# Sheet1.net
KiCad netlist of a schematic drawn in Altium Designer
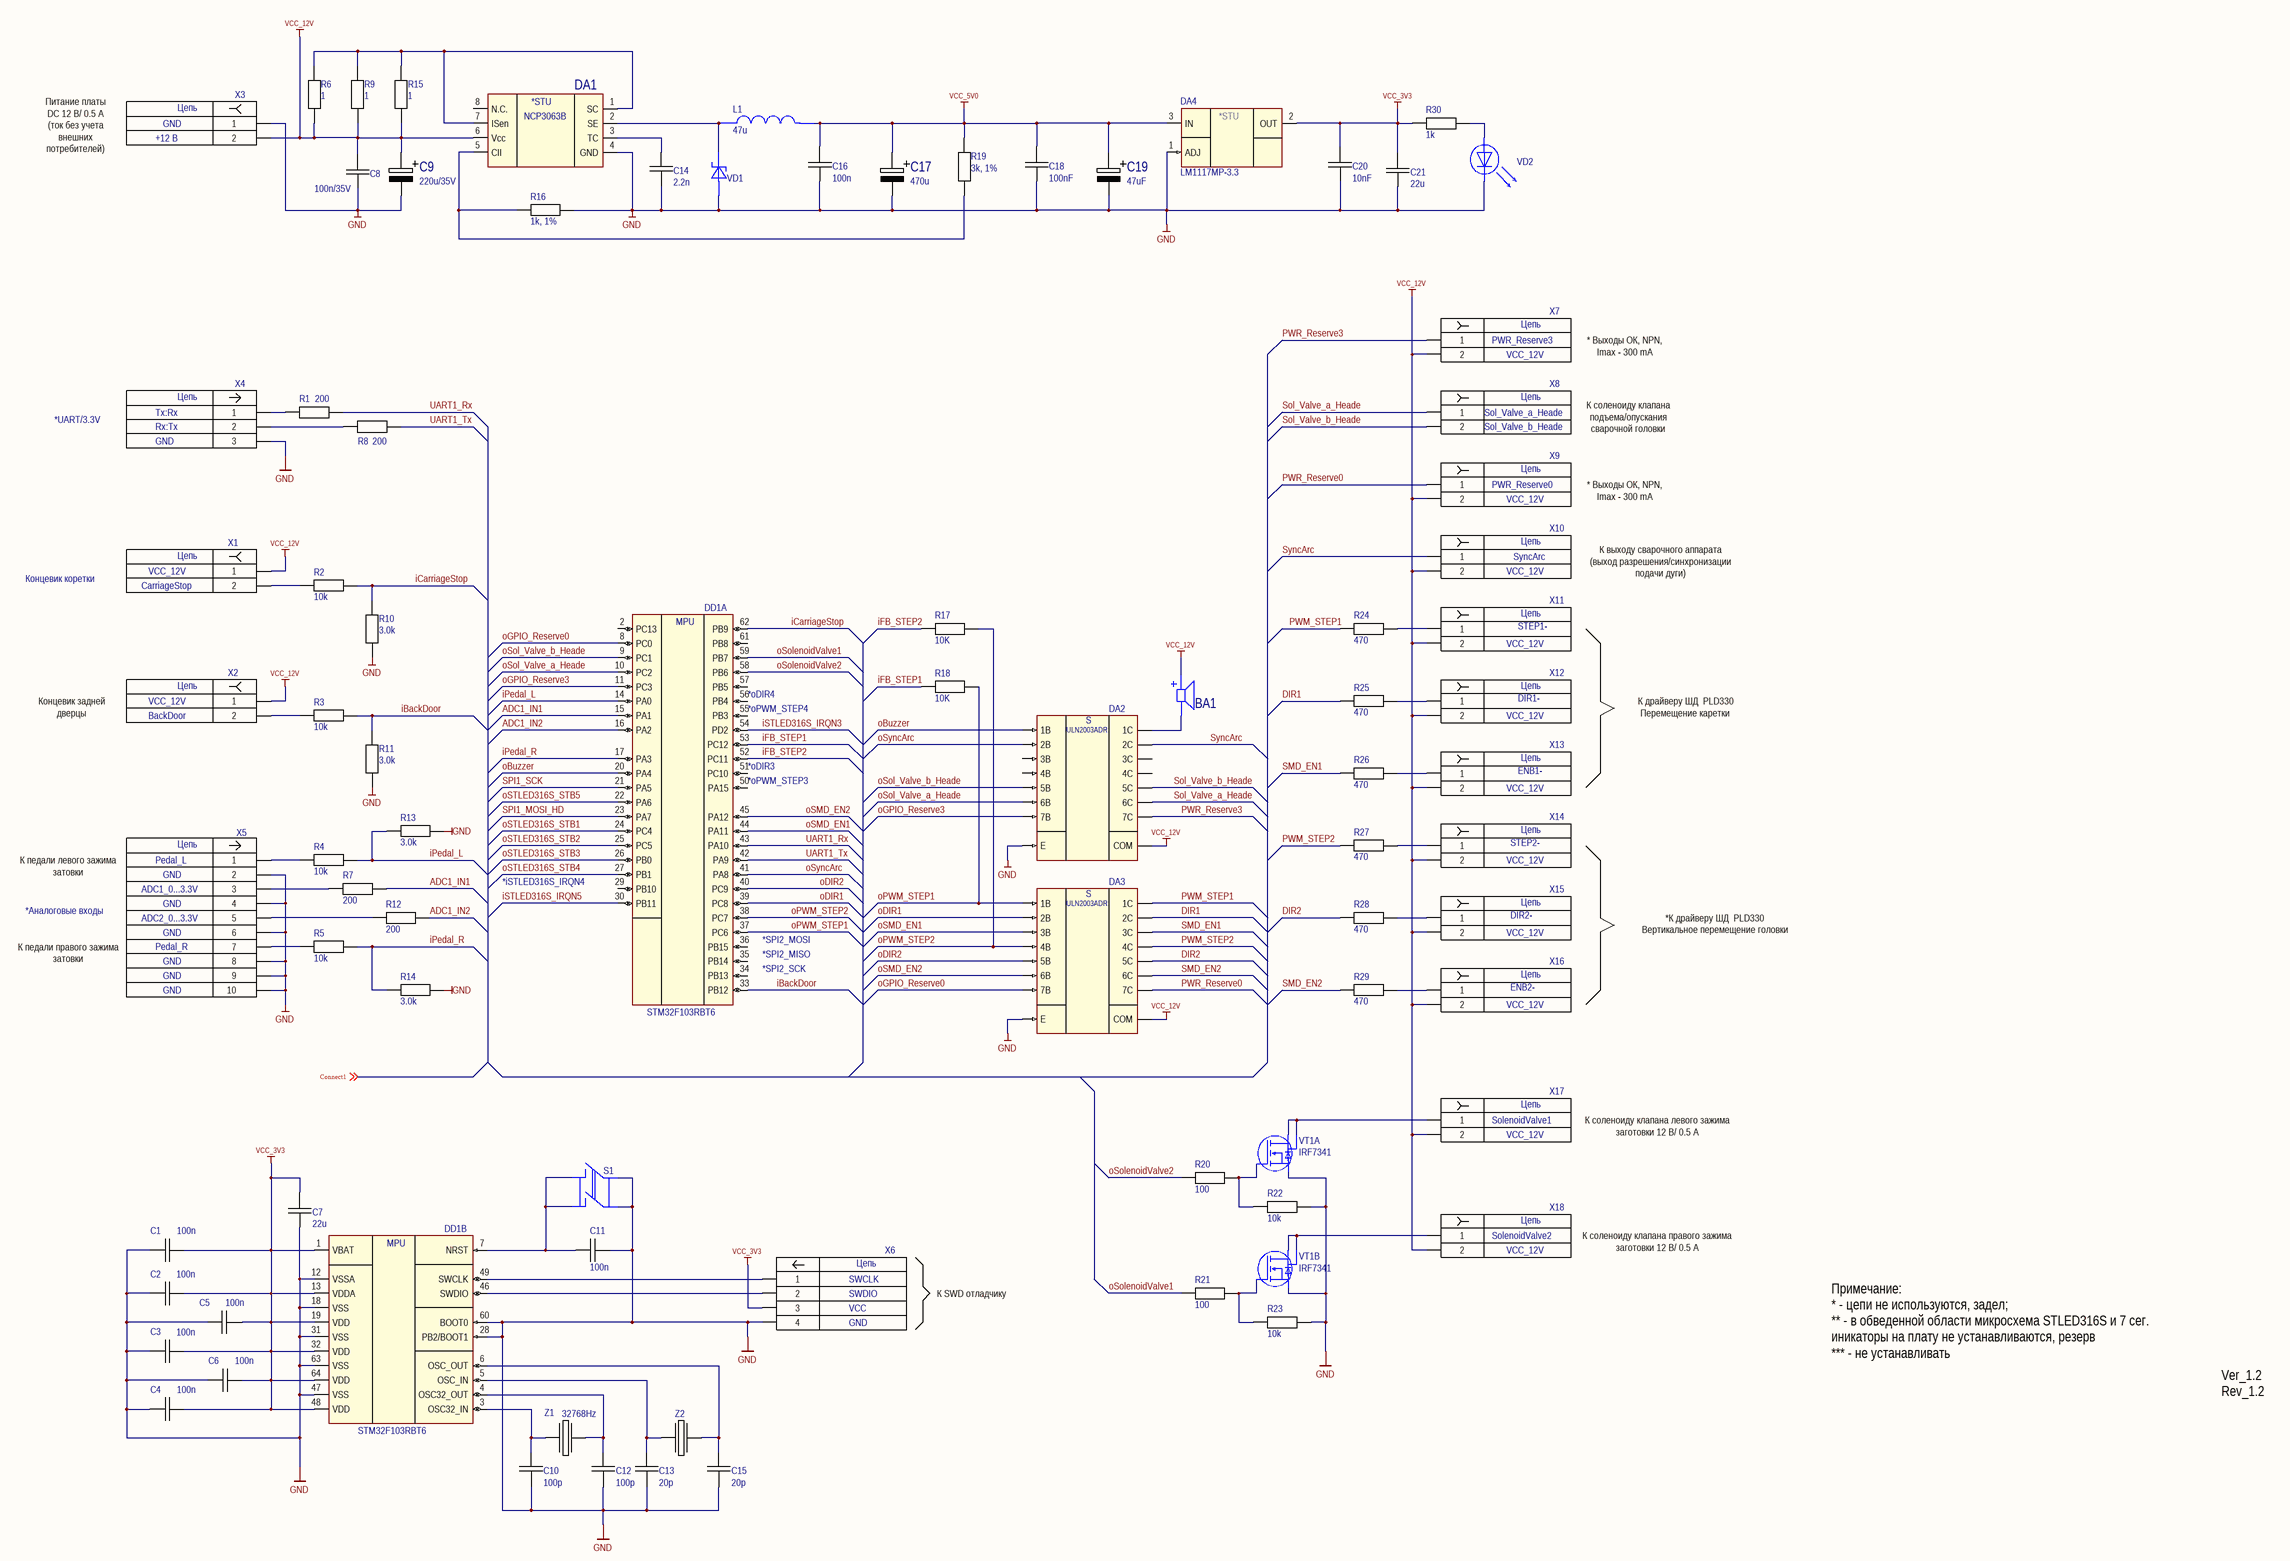
[diagram p0: Sheet1.SchDoc]

(export (version "E")
  (design (tool "Eeschema 10.0.6"))
  (components
    (comp (ref "BA1")
      (value "Buzzer_HCM1212A")
      (footprint "Buzzer_HCM1212A")
      (libsource (lib "Библиотека элементов") (part "Buzzer_HCM1212A"))
    )
    (comp (ref "C1")
      (value "100n")
      (footprint "Capacitor_0805")
      (libsource (lib "Библиотека элементов") (part "Capacitor_0805"))
    )
    (comp (ref "C2")
      (value "100n")
      (footprint "Capacitor_0805")
      (libsource (lib "Библиотека элементов") (part "Capacitor_0805"))
    )
    (comp (ref "C3")
      (value "100n")
      (footprint "Capacitor_0805")
      (libsource (lib "Библиотека элементов") (part "Capacitor_0805"))
    )
    (comp (ref "C4")
      (value "100n")
      (footprint "Capacitor_0805")
      (libsource (lib "Библиотека элементов") (part "Capacitor_0805"))
    )
    (comp (ref "C5")
      (value "100n")
      (footprint "Capacitor_0805")
      (libsource (lib "Библиотека элементов") (part "Capacitor_0805"))
    )
    (comp (ref "C6")
      (value "100n")
      (footprint "Capacitor_0805")
      (libsource (lib "Библиотека элементов") (part "Capacitor_0805"))
    )
    (comp (ref "C7")
      (value "22u")
      (footprint "CAPACITOR_1206")
      (libsource (lib "Библиотека элементов") (part "Capacitor_1206"))
    )
    (comp (ref "C8")
      (value "100n/35V")
      (footprint "Capacitor_0805")
      (libsource (lib "Библиотека элементов") (part "Capacitor_0805"))
    )
    (comp (ref "C9")
      (value "220u/35V")
      (footprint "Capacitor_Electrolit_6.3x11")
      (libsource (lib "Библиотека элементов") (part "Capacitor+_6.3x11"))
    )
    (comp (ref "C10")
      (value "100p")
      (footprint "Capacitor_0805")
      (libsource (lib "Библиотека элементов") (part "Capacitor_0805"))
    )
    (comp (ref "C11")
      (value "100n")
      (footprint "Capacitor_0805")
      (libsource (lib "Библиотека элементов") (part "Capacitor_0805"))
    )
    (comp (ref "C12")
      (value "100p")
      (footprint "Capacitor_0805")
      (libsource (lib "Библиотека элементов") (part "Capacitor_0805"))
    )
    (comp (ref "C13")
      (value "20p")
      (footprint "Capacitor_0805")
      (libsource (lib "Библиотека элементов") (part "Capacitor_0805"))
    )
    (comp (ref "C14")
      (value "2.2n")
      (footprint "Capacitor_0805")
      (libsource (lib "Библиотека элементов") (part "Capacitor_0805"))
    )
    (comp (ref "C15")
      (value "20p")
      (footprint "Capacitor_0805")
      (libsource (lib "Библиотека элементов") (part "Capacitor_0805"))
    )
    (comp (ref "C16")
      (value "100n")
      (footprint "Capacitor_0805")
      (libsource (lib "Библиотека элементов") (part "Capacitor_0805"))
    )
    (comp (ref "C17")
      (value "470u")
      (footprint "Capacitor_Electrolit_6.3x11")
      (libsource (lib "Библиотека элементов") (part "Capacitor+_6.3x11"))
    )
    (comp (ref "C18")
      (value "100nF")
      (footprint "Capacitor_0805")
      (libsource (lib "Библиотека элементов") (part "Capacitor_0805"))
    )
    (comp (ref "C19")
      (value "47uF")
      (footprint "Capacitor_Electrolit_6.3x11")
      (libsource (lib "Библиотека элементов") (part "Capacitor+_6.3x11"))
    )
    (comp (ref "C20")
      (value "10nF")
      (footprint "Capacitor_0805")
      (libsource (lib "Библиотека элементов") (part "Capacitor_0805"))
    )
    (comp (ref "C21")
      (value "22u")
      (footprint "CAPACITOR_1206")
      (libsource (lib "Библиотека элементов") (part "Capacitor_1206"))
    )
    (comp (ref "DA1")
      (value "NCP3063B")
      (footprint "SOIC8")
      (libsource (lib "Библиотека элементов") (part "NCP3063B"))
    )
    (comp (ref "DA2")
      (value "ULN2003")
      (footprint "MCP3208_SOIC16")
      (libsource (lib "Библиотека элементов") (part "ULN2003"))
    )
    (comp (ref "DA3")
      (value "ULN2003")
      (footprint "MCP3208_SOIC16")
      (libsource (lib "Библиотека элементов") (part "ULN2003"))
    )
    (comp (ref "DA4")
      (value "LM1117MP-3.3")
      (footprint "NCP1117_SOT223")
      (libsource (lib "Библиотека элементов") (part "LM1117MP-3.3"))
    )
    (comp (ref "DD1")
      (value "STM32F103RBT6")
      (footprint "STM32F103RBT6_LQFP64")
      (libsource (lib "Библиотека элементов") (part "STM32F103RBT6"))
    )
    (comp (ref "L1")
      (value "47u")
      (footprint "INDUCTOR_CDRH8D28")
      (libsource (lib "Библиотека элементов") (part "Indluctor_CDRH8D28"))
    )
    (comp (ref "R1")
      (value "200")
      (footprint "RESISTOR_SMD0805")
      (libsource (lib "Библиотека элементов") (part "Resistor_0805"))
    )
    (comp (ref "R2")
      (value "10k")
      (footprint "RESISTOR_SMD0805")
      (libsource (lib "Библиотека элементов") (part "Resistor_0805"))
    )
    (comp (ref "R3")
      (value "10k")
      (footprint "RESISTOR_SMD0805")
      (libsource (lib "Библиотека элементов") (part "Resistor_0805"))
    )
    (comp (ref "R4")
      (value "10k")
      (footprint "RESISTOR_SMD0805")
      (libsource (lib "Библиотека элементов") (part "Resistor_0805"))
    )
    (comp (ref "R5")
      (value "10k")
      (footprint "RESISTOR_SMD0805")
      (libsource (lib "Библиотека элементов") (part "Resistor_0805"))
    )
    (comp (ref "R6")
      (value "1")
      (footprint "RESISTOR_SMD0805")
      (libsource (lib "Библиотека элементов") (part "Resistor_0805"))
    )
    (comp (ref "R7")
      (value "200")
      (footprint "RESISTOR_SMD0805")
      (libsource (lib "Библиотека элементов") (part "Resistor_0805"))
    )
    (comp (ref "R8")
      (value "200")
      (footprint "RESISTOR_SMD0805")
      (libsource (lib "Библиотека элементов") (part "Resistor_0805"))
    )
    (comp (ref "R9")
      (value "1")
      (footprint "RESISTOR_SMD0805")
      (libsource (lib "Библиотека элементов") (part "Resistor_0805"))
    )
    (comp (ref "R10")
      (value "3.0k")
      (footprint "RESISTOR_SMD0805")
      (libsource (lib "Библиотека элементов") (part "Resistor_0805"))
    )
    (comp (ref "R11")
      (value "3.0k")
      (footprint "RESISTOR_SMD0805")
      (libsource (lib "Библиотека элементов") (part "Resistor_0805"))
    )
    (comp (ref "R12")
      (value "200")
      (footprint "RESISTOR_SMD0805")
      (libsource (lib "Библиотека элементов") (part "Resistor_0805"))
    )
    (comp (ref "R13")
      (value "3.0k")
      (footprint "RESISTOR_SMD0805")
      (libsource (lib "Библиотека элементов") (part "Resistor_0805"))
    )
    (comp (ref "R14")
      (value "3.0k")
      (footprint "RESISTOR_SMD0805")
      (libsource (lib "Библиотека элементов") (part "Resistor_0805"))
    )
    (comp (ref "R15")
      (value "1")
      (footprint "RESISTOR_SMD0805")
      (libsource (lib "Библиотека элементов") (part "Resistor_0805"))
    )
    (comp (ref "R16")
      (value "1k, 1%")
      (footprint "RESISTOR_SMD0805")
      (libsource (lib "Библиотека элементов") (part "Resistor_0805"))
    )
    (comp (ref "R17")
      (value "10K")
      (footprint "RESISTOR_SMD0805")
      (libsource (lib "Библиотека элементов") (part "Resistor_0805"))
    )
    (comp (ref "R18")
      (value "10K")
      (footprint "RESISTOR_SMD0805")
      (libsource (lib "Библиотека элементов") (part "Resistor_0805"))
    )
    (comp (ref "R19")
      (value "3k, 1%")
      (footprint "RESISTOR_SMD0805")
      (libsource (lib "Библиотека элементов") (part "Resistor_0805"))
    )
    (comp (ref "R20")
      (value "100")
      (footprint "RESISTOR_SMD0805")
      (libsource (lib "Библиотека элементов") (part "Resistor_0805"))
    )
    (comp (ref "R21")
      (value "100")
      (footprint "RESISTOR_SMD0805")
      (libsource (lib "Библиотека элементов") (part "Resistor_0805"))
    )
    (comp (ref "R22")
      (value "10k")
      (footprint "RESISTOR_SMD0805")
      (libsource (lib "Библиотека элементов") (part "Resistor_0805"))
    )
    (comp (ref "R23")
      (value "10k")
      (footprint "RESISTOR_SMD0805")
      (libsource (lib "Библиотека элементов") (part "Resistor_0805"))
    )
    (comp (ref "R24")
      (value "470")
      (footprint "RESISTOR_SMD0805")
      (libsource (lib "Библиотека элементов") (part "Resistor_0805"))
    )
    (comp (ref "R25")
      (value "470")
      (footprint "RESISTOR_SMD0805")
      (libsource (lib "Библиотека элементов") (part "Resistor_0805"))
    )
    (comp (ref "R26")
      (value "470")
      (footprint "RESISTOR_SMD0805")
      (libsource (lib "Библиотека элементов") (part "Resistor_0805"))
    )
    (comp (ref "R27")
      (value "470")
      (footprint "RESISTOR_SMD0805")
      (libsource (lib "Библиотека элементов") (part "Resistor_0805"))
    )
    (comp (ref "R28")
      (value "470")
      (footprint "RESISTOR_SMD0805")
      (libsource (lib "Библиотека элементов") (part "Resistor_0805"))
    )
    (comp (ref "R29")
      (value "470")
      (footprint "RESISTOR_SMD0805")
      (libsource (lib "Библиотека элементов") (part "Resistor_0805"))
    )
    (comp (ref "R30")
      (value "1k")
      (footprint "RESISTOR_SMD0805")
      (libsource (lib "") (part "Resistor_0805_1"))
    )
    (comp (ref "S1")
      (value "DTS-26 12x12x9.5")
      (footprint "Tact Switch_DTS-26_12x12x95")
      (libsource (lib "Библиотека элементов") (part "Tact_Switch_DTS-26_12x12x95"))
    )
    (comp (ref "VD1")
      (value "STPS1L30A")
      (footprint "DIODE_STPS1L30A")
      (libsource (lib "Библиотека элементов") (part "Diode_STPS1L30A"))
    )
    (comp (ref "VD2")
      (value "LED_FYL-3014GD1A")
      (footprint "LED_ FYL-3014GD1A")
      (libsource (lib "Библиотека элементов") (part "LED_FYL-3014GD1A"))
    )
    (comp (ref "VT1")
      (value "IRF7341")
      (footprint "IRF7341_SO-8/SOIC-8")
      (libsource (lib "Библиотека элементов") (part "IRF7341"))
    )
    (comp (ref "X1")
      (value "Connector_DG306-5.0-02P")
      (footprint "CONNECTOR_DG306-5.0-02P")
      (libsource (lib "Библиотека элементов") (part "Connector_DG306-5.0-02P"))
    )
    (comp (ref "X2")
      (value "Connector_DG306-5.0-02P")
      (footprint "CONNECTOR_DG306-5.0-02P")
      (libsource (lib "Библиотека элементов") (part "Connector_DG306-5.0-02P"))
    )
    (comp (ref "X3")
      (value "Connector_DG306-5.0-02P")
      (footprint "CONNECTOR_DG306-5.0-02P")
      (libsource (lib "Библиотека элементов") (part "Connector_DG306-5.0-02P"))
    )
    (comp (ref "X4")
      (value "Connector_PLS-3")
      (footprint "CONNECTOR_PLS-3")
      (libsource (lib "Библиотека элементов") (part "Connector_PLS-3"))
    )
    (comp (ref "X5")
      (value "Connector_PLD-10")
      (footprint "CONNECTOR_PLD-10")
      (libsource (lib "Библиотека элементов") (part "Connector_PLD-10"))
    )
    (comp (ref "X6")
      (value "Connector_PLS-4")
      (footprint "CONNECTOR_PLS-4")
      (libsource (lib "Библиотека элементов") (part "Connector_PLS-4"))
    )
    (comp (ref "X7")
      (value "Connector_DG306-5.0-02P")
      (footprint "CONNECTOR_DG306-5.0-02P")
      (libsource (lib "Библиотека элементов") (part "Connector_DG306-5.0-02P"))
    )
    (comp (ref "X8")
      (value "Connector_DG306-5.0-02P")
      (footprint "CONNECTOR_DG306-5.0-02P")
      (libsource (lib "Библиотека элементов") (part "Connector_DG306-5.0-02P"))
    )
    (comp (ref "X9")
      (value "Connector_DG306-5.0-02P")
      (footprint "CONNECTOR_DG306-5.0-02P")
      (libsource (lib "Библиотека элементов") (part "Connector_DG306-5.0-02P"))
    )
    (comp (ref "X10")
      (value "Connector_DG306-5.0-02P")
      (footprint "CONNECTOR_DG306-5.0-02P")
      (libsource (lib "Библиотека элементов") (part "Connector_DG306-5.0-02P"))
    )
    (comp (ref "X11")
      (value "Connector_DG306-5.0-02P")
      (footprint "CONNECTOR_DG306-5.0-02P")
      (libsource (lib "Библиотека элементов") (part "Connector_DG306-5.0-02P"))
    )
    (comp (ref "X12")
      (value "Connector_DG306-5.0-02P")
      (footprint "CONNECTOR_DG306-5.0-02P")
      (libsource (lib "Библиотека элементов") (part "Connector_DG306-5.0-02P"))
    )
    (comp (ref "X13")
      (value "Connector_DG306-5.0-02P")
      (footprint "CONNECTOR_DG306-5.0-02P")
      (libsource (lib "Библиотека элементов") (part "Connector_DG306-5.0-02P"))
    )
    (comp (ref "X14")
      (value "Connector_DG306-5.0-02P")
      (footprint "CONNECTOR_DG306-5.0-02P")
      (libsource (lib "Библиотека элементов") (part "Connector_DG306-5.0-02P"))
    )
    (comp (ref "X15")
      (value "Connector_DG306-5.0-02P")
      (footprint "CONNECTOR_DG306-5.0-02P")
      (libsource (lib "Библиотека элементов") (part "Connector_DG306-5.0-02P"))
    )
    (comp (ref "X16")
      (value "Connector_DG306-5.0-02P")
      (footprint "CONNECTOR_DG306-5.0-02P")
      (libsource (lib "Библиотека элементов") (part "Connector_DG306-5.0-02P"))
    )
    (comp (ref "X17")
      (value "Connector_DG306-5.0-02P")
      (footprint "CONNECTOR_DG306-5.0-02P")
      (libsource (lib "Библиотека элементов") (part "Connector_DG306-5.0-02P"))
    )
    (comp (ref "X18")
      (value "Connector_DG306-5.0-02P")
      (footprint "CONNECTOR_DG306-5.0-02P")
      (libsource (lib "Библиотека элементов") (part "Connector_DG306-5.0-02P"))
    )
    (comp (ref "Z1")
      (value "32768Hz")
      (footprint "Quartz_32768kHz")
      (libsource (lib "Библиотека элементов") (part "Quartz_32678Hz"))
    )
    (comp (ref "Z2")
      (value "Quartz_KX-9A")
      (footprint "Quartz_KX-9")
      (libsource (lib "Библиотека элементов") (part "Quartz_KX-9A"))
    )
  )
  (nets
    (net (code "1") (name "/ADC1_IN1") (class "Default")
      (node (ref "DD1") (pin "15") (pinfunction "PA1_15") (pintype "bidirectional"))
      (node (ref "R7") (pin "1") (pinfunction "1_1") (pintype "passive"))
    )
    (net (code "2") (name "/ADC1_IN2") (class "Default")
      (node (ref "DD1") (pin "16") (pinfunction "PA2_16") (pintype "bidirectional"))
      (node (ref "R12") (pin "1") (pinfunction "1_1") (pintype "passive"))
    )
    (net (code "3") (name "/DIR1") (class "Default")
      (node (ref "DA3") (pin "15") (pinfunction "2C_15") (pintype "open_collector"))
      (node (ref "R25") (pin "2") (pinfunction "2_2") (pintype "passive"))
    )
    (net (code "4") (name "/DIR2") (class "Default")
      (node (ref "DA3") (pin "12") (pinfunction "5C_12") (pintype "open_collector"))
      (node (ref "R28") (pin "2") (pinfunction "2_2") (pintype "passive"))
    )
    (net (code "5") (name "/PWM_STEP1") (class "Default")
      (node (ref "DA3") (pin "16") (pinfunction "1C_16") (pintype "open_collector"))
      (node (ref "R24") (pin "2") (pinfunction "2_2") (pintype "passive"))
    )
    (net (code "6") (name "/PWM_STEP2") (class "Default")
      (node (ref "DA3") (pin "13") (pinfunction "4C_13") (pintype "open_collector"))
      (node (ref "R27") (pin "2") (pinfunction "2_2") (pintype "passive"))
    )
    (net (code "7") (name "/PWR_Reserve0") (class "Default")
      (node (ref "DA3") (pin "10") (pinfunction "7C_10") (pintype "open_collector"))
      (node (ref "X9") (pin "1") (pinfunction "1_1") (pintype "passive"))
    )
    (net (code "8") (name "/PWR_Reserve3") (class "Default")
      (node (ref "DA2") (pin "10") (pinfunction "7C_10") (pintype "open_collector"))
      (node (ref "X7") (pin "1") (pinfunction "1_1") (pintype "passive"))
    )
    (net (code "9") (name "/SMD_EN1") (class "Default")
      (node (ref "DA3") (pin "14") (pinfunction "3C_14") (pintype "open_collector"))
      (node (ref "R26") (pin "2") (pinfunction "2_2") (pintype "passive"))
    )
    (net (code "10") (name "/SMD_EN2") (class "Default")
      (node (ref "DA3") (pin "11") (pinfunction "6C_11") (pintype "open_collector"))
      (node (ref "R29") (pin "2") (pinfunction "2_2") (pintype "passive"))
    )
    (net (code "11") (name "/SPI1_MOSI_HD") (class "Default")
      (node (ref "DD1") (pin "23") (pinfunction "PA7_23") (pintype "bidirectional"))
    )
    (net (code "12") (name "/SPI1_SCK") (class "Default")
      (node (ref "DD1") (pin "21") (pinfunction "PA5_21") (pintype "bidirectional"))
    )
    (net (code "13") (name "/Sol_Valve_a_Heade") (class "Default")
      (node (ref "DA2") (pin "11") (pinfunction "6C_11") (pintype "open_collector"))
      (node (ref "X8") (pin "1") (pinfunction "1_1") (pintype "passive"))
    )
    (net (code "14") (name "/Sol_Valve_b_Heade") (class "Default")
      (node (ref "DA2") (pin "12") (pinfunction "5C_12") (pintype "open_collector"))
      (node (ref "X8") (pin "2") (pinfunction "2_2") (pintype "passive"))
    )
    (net (code "15") (name "/SyncArc") (class "Default")
      (node (ref "DA2") (pin "15") (pinfunction "2C_15") (pintype "open_collector"))
      (node (ref "X10") (pin "1") (pinfunction "1_1") (pintype "passive"))
    )
    (net (code "16") (name "/UART1_Rx") (class "Default")
      (node (ref "DD1") (pin "43") (pinfunction "PA10_43") (pintype "bidirectional"))
      (node (ref "R1") (pin "1") (pinfunction "1_1") (pintype "passive"))
    )
    (net (code "17") (name "/UART1_Tx") (class "Default")
      (node (ref "DD1") (pin "42") (pinfunction "PA9_42") (pintype "bidirectional"))
      (node (ref "R8") (pin "1") (pinfunction "1_1") (pintype "passive"))
    )
    (net (code "18") (name "/iBackDoor") (class "Default")
      (node (ref "DD1") (pin "33") (pinfunction "PB12_33") (pintype "bidirectional"))
      (node (ref "R11") (pin "2") (pinfunction "2_2") (pintype "passive"))
      (node (ref "R3") (pin "1") (pinfunction "1_1") (pintype "passive"))
    )
    (net (code "19") (name "/iCarriageStop") (class "Default")
      (node (ref "DD1") (pin "62") (pinfunction "PB9_62") (pintype "bidirectional"))
      (node (ref "R10") (pin "2") (pinfunction "2_2") (pintype "passive"))
      (node (ref "R2") (pin "1") (pinfunction "1_1") (pintype "passive"))
    )
    (net (code "20") (name "/iFB_STEP1") (class "Default")
      (node (ref "DD1") (pin "53") (pinfunction "PC12_53") (pintype "bidirectional"))
      (node (ref "R18") (pin "1") (pinfunction "1_1") (pintype "passive"))
    )
    (net (code "21") (name "/iFB_STEP2") (class "Default")
      (node (ref "DD1") (pin "52") (pinfunction "PC11_52") (pintype "bidirectional"))
      (node (ref "R17") (pin "1") (pinfunction "1_1") (pintype "passive"))
    )
    (net (code "22") (name "/iPedal_L") (class "Default")
      (node (ref "DD1") (pin "14") (pinfunction "PA0_14") (pintype "bidirectional"))
      (node (ref "R13") (pin "2") (pinfunction "2_2") (pintype "passive"))
      (node (ref "R4") (pin "1") (pinfunction "1_1") (pintype "passive"))
    )
    (net (code "23") (name "/iPedal_R") (class "Default")
      (node (ref "DD1") (pin "17") (pinfunction "PA3_17") (pintype "bidirectional"))
      (node (ref "R14") (pin "2") (pinfunction "2_2") (pintype "passive"))
      (node (ref "R5") (pin "1") (pinfunction "1_1") (pintype "passive"))
    )
    (net (code "24") (name "/iSTLED316S_IRQN3") (class "Default")
      (node (ref "DD1") (pin "54") (pinfunction "PD2_54") (pintype "bidirectional"))
    )
    (net (code "25") (name "/iSTLED316S_IRQN5") (class "Default")
      (node (ref "DD1") (pin "30") (pinfunction "PB11_30") (pintype "bidirectional"))
    )
    (net (code "26") (name "/oBuzzer") (class "Default")
      (node (ref "DA2") (pin "1") (pinfunction "1B_1") (pintype "input"))
      (node (ref "DD1") (pin "20") (pinfunction "PA4_20") (pintype "bidirectional"))
    )
    (net (code "27") (name "/oDIR1") (class "Default")
      (node (ref "DA3") (pin "2") (pinfunction "2B_2") (pintype "input"))
      (node (ref "DD1") (pin "39") (pinfunction "PC8_39") (pintype "bidirectional"))
    )
    (net (code "28") (name "/oDIR2") (class "Default")
      (node (ref "DA3") (pin "5") (pinfunction "5B_5") (pintype "input"))
      (node (ref "DD1") (pin "40") (pinfunction "PC9_40") (pintype "bidirectional"))
    )
    (net (code "29") (name "/oGPIO_Reserve0") (class "Default")
      (node (ref "DA3") (pin "7") (pinfunction "7B_7") (pintype "input"))
      (node (ref "DD1") (pin "8") (pinfunction "PC0_8") (pintype "bidirectional"))
    )
    (net (code "30") (name "/oGPIO_Reserve3") (class "Default")
      (node (ref "DA2") (pin "7") (pinfunction "7B_7") (pintype "input"))
      (node (ref "DD1") (pin "11") (pinfunction "PC3_11") (pintype "bidirectional"))
    )
    (net (code "31") (name "/oPWM_STEP1") (class "Default")
      (node (ref "DA3") (pin "1") (pinfunction "1B_1") (pintype "input"))
      (node (ref "DD1") (pin "37") (pinfunction "PC6_37") (pintype "bidirectional"))
      (node (ref "R18") (pin "2") (pinfunction "2_2") (pintype "passive"))
    )
    (net (code "32") (name "/oPWM_STEP2") (class "Default")
      (node (ref "DA3") (pin "4") (pinfunction "4B_4") (pintype "input"))
      (node (ref "DD1") (pin "38") (pinfunction "PC7_38") (pintype "bidirectional"))
      (node (ref "R17") (pin "2") (pinfunction "2_2") (pintype "passive"))
    )
    (net (code "33") (name "/oSMD_EN1") (class "Default")
      (node (ref "DA3") (pin "3") (pinfunction "3B_3") (pintype "input"))
      (node (ref "DD1") (pin "44") (pinfunction "PA11_44") (pintype "bidirectional"))
    )
    (net (code "34") (name "/oSMD_EN2") (class "Default")
      (node (ref "DA3") (pin "6") (pinfunction "6B_6") (pintype "input"))
      (node (ref "DD1") (pin "45") (pinfunction "PA12_45") (pintype "bidirectional"))
    )
    (net (code "35") (name "/oSTLED316S_STB1") (class "Default")
      (node (ref "DD1") (pin "24") (pinfunction "PC4_24") (pintype "bidirectional"))
    )
    (net (code "36") (name "/oSTLED316S_STB2") (class "Default")
      (node (ref "DD1") (pin "25") (pinfunction "PC5_25") (pintype "bidirectional"))
    )
    (net (code "37") (name "/oSTLED316S_STB3") (class "Default")
      (node (ref "DD1") (pin "26") (pinfunction "PB0_26") (pintype "bidirectional"))
    )
    (net (code "38") (name "/oSTLED316S_STB4") (class "Default")
      (node (ref "DD1") (pin "27") (pinfunction "PB1_27") (pintype "bidirectional"))
    )
    (net (code "39") (name "/oSTLED316S_STB5") (class "Default")
      (node (ref "DD1") (pin "22") (pinfunction "PA6_22") (pintype "bidirectional"))
    )
    (net (code "40") (name "/oSol_Valve_a_Heade") (class "Default")
      (node (ref "DA2") (pin "6") (pinfunction "6B_6") (pintype "input"))
      (node (ref "DD1") (pin "10") (pinfunction "PC2_10") (pintype "bidirectional"))
    )
    (net (code "41") (name "/oSol_Valve_b_Heade") (class "Default")
      (node (ref "DA2") (pin "5") (pinfunction "5B_5") (pintype "input"))
      (node (ref "DD1") (pin "9") (pinfunction "PC1_9") (pintype "bidirectional"))
    )
    (net (code "42") (name "/oSolenoidValve1") (class "Default")
      (node (ref "DD1") (pin "59") (pinfunction "PB7_59") (pintype "bidirectional"))
      (node (ref "R21") (pin "2") (pinfunction "2_2") (pintype "passive"))
    )
    (net (code "43") (name "/oSolenoidValve2") (class "Default")
      (node (ref "DD1") (pin "58") (pinfunction "PB6_58") (pintype "bidirectional"))
      (node (ref "R20") (pin "2") (pinfunction "2_2") (pintype "passive"))
    )
    (net (code "44") (name "/oSyncArc") (class "Default")
      (node (ref "DA2") (pin "2") (pinfunction "2B_2") (pintype "input"))
      (node (ref "DD1") (pin "41") (pinfunction "PA8_41") (pintype "bidirectional"))
    )
    (net (code "46") (name "GND") (class "Default")
      (node (ref "C1") (pin "1") (pinfunction "1_1") (pintype "passive"))
      (node (ref "C10") (pin "1") (pinfunction "1_1") (pintype "passive"))
      (node (ref "C11") (pin "1") (pinfunction "1_1") (pintype "passive"))
      (node (ref "C12") (pin "1") (pinfunction "1_1") (pintype "passive"))
      (node (ref "C13") (pin "1") (pinfunction "1_1") (pintype "passive"))
      (node (ref "C14") (pin "1") (pinfunction "1_1") (pintype "passive"))
      (node (ref "C15") (pin "1") (pinfunction "1_1") (pintype "passive"))
      (node (ref "C16") (pin "2") (pinfunction "2_2") (pintype "passive"))
      (node (ref "C17") (pin "2") (pinfunction "2_2") (pintype "passive"))
      (node (ref "C18") (pin "2") (pinfunction "2_2") (pintype "passive"))
      (node (ref "C19") (pin "2") (pinfunction "2_2") (pintype "passive"))
      (node (ref "C2") (pin "1") (pinfunction "1_1") (pintype "passive"))
      (node (ref "C20") (pin "2") (pinfunction "2_2") (pintype "passive"))
      (node (ref "C21") (pin "2") (pinfunction "2_2") (pintype "passive"))
      (node (ref "C3") (pin "1") (pinfunction "1_1") (pintype "passive"))
      (node (ref "C4") (pin "1") (pinfunction "1_1") (pintype "passive"))
      (node (ref "C5") (pin "2") (pinfunction "2_2") (pintype "passive"))
      (node (ref "C6") (pin "1") (pinfunction "1_1") (pintype "passive"))
      (node (ref "C7") (pin "2") (pinfunction "2_2") (pintype "passive"))
      (node (ref "C8") (pin "2") (pinfunction "2_2") (pintype "passive"))
      (node (ref "C9") (pin "2") (pinfunction "2_2") (pintype "passive"))
      (node (ref "DA1") (pin "4") (pinfunction "GND_4") (pintype "power_in"))
      (node (ref "DA2") (pin "8") (pinfunction "E_8") (pintype "input"))
      (node (ref "DA3") (pin "8") (pinfunction "E_8") (pintype "input"))
      (node (ref "DA4") (pin "1") (pinfunction "ADJ_1") (pintype "input"))
      (node (ref "DD1") (pin "12") (pinfunction "VSSA_12") (pintype "power_in"))
      (node (ref "DD1") (pin "18") (pinfunction "VSS_18") (pintype "power_in"))
      (node (ref "DD1") (pin "28") (pinfunction "PB2/BOOT1_28") (pintype "input"))
      (node (ref "DD1") (pin "31") (pinfunction "VSS_31") (pintype "power_in"))
      (node (ref "DD1") (pin "47") (pinfunction "VSS_47") (pintype "power_in"))
      (node (ref "DD1") (pin "60") (pinfunction "BOOT0_60") (pintype "input"))
      (node (ref "DD1") (pin "63") (pinfunction "VSS_63") (pintype "power_in"))
      (node (ref "R10") (pin "1") (pinfunction "1_1") (pintype "passive"))
      (node (ref "R11") (pin "1") (pinfunction "1_1") (pintype "passive"))
      (node (ref "R13") (pin "1") (pinfunction "1_1") (pintype "passive"))
      (node (ref "R14") (pin "1") (pinfunction "1_1") (pintype "passive"))
      (node (ref "R16") (pin "1") (pinfunction "1_1") (pintype "passive"))
      (node (ref "R22") (pin "1") (pinfunction "1_1") (pintype "passive"))
      (node (ref "R23") (pin "1") (pinfunction "1_1") (pintype "passive"))
      (node (ref "S1") (pin "3") (pintype "passive"))
      (node (ref "S1") (pin "4") (pintype "passive"))
      (node (ref "VD1") (pin "2") (pinfunction "2_2") (pintype "passive"))
      (node (ref "VD2") (pin "1") (pinfunction "1_1") (pintype "passive"))
      (node (ref "VT1") (pin "1") (pinfunction "1_1") (pintype "passive"))
      (node (ref "VT1") (pin "3") (pinfunction "3_3") (pintype "passive"))
      (node (ref "X3") (pin "1") (pinfunction "1_1") (pintype "passive"))
      (node (ref "X4") (pin "3") (pinfunction "3_3") (pintype "passive"))
      (node (ref "X5") (pin "10") (pinfunction "10_10") (pintype "passive"))
      (node (ref "X5") (pin "2") (pinfunction "2_2") (pintype "passive"))
      (node (ref "X5") (pin "4") (pinfunction "4_4") (pintype "passive"))
      (node (ref "X5") (pin "6") (pinfunction "6_6") (pintype "passive"))
      (node (ref "X5") (pin "8") (pinfunction "8_8") (pintype "passive"))
      (node (ref "X5") (pin "9") (pinfunction "9_9") (pintype "passive"))
      (node (ref "X6") (pin "4") (pinfunction "4_4") (pintype "passive"))
    )
    (net (code "47") (name "Net-(DA1-CII)") (class "Default")
      (node (ref "DA1") (pin "5") (pinfunction "CII_5") (pintype "passive"))
      (node (ref "R16") (pin "2") (pinfunction "2_2") (pintype "passive"))
      (node (ref "R19") (pin "2") (pinfunction "2_2") (pintype "passive"))
    )
    (net (code "48") (name "Net-(DA1-ISen)") (class "Default")
      (node (ref "DA1") (pin "1") (pinfunction "SC_1") (pintype "passive"))
      (node (ref "DA1") (pin "7") (pinfunction "ISen_7") (pintype "passive"))
      (node (ref "R15") (pin "1") (pinfunction "1_1") (pintype "passive"))
      (node (ref "R6") (pin "1") (pinfunction "1_1") (pintype "passive"))
      (node (ref "R9") (pin "1") (pinfunction "1_1") (pintype "passive"))
    )
    (net (code "49") (name "Net-(DA1-SE)") (class "Default")
      (node (ref "DA1") (pin "2") (pinfunction "SE_2") (pintype "passive"))
      (node (ref "L1") (pin "1") (pinfunction "1_1") (pintype "passive"))
      (node (ref "VD1") (pin "1") (pinfunction "1_1") (pintype "passive"))
    )
    (net (code "50") (name "Net-(DA1-TC)") (class "Default")
      (node (ref "C14") (pin "2") (pinfunction "2_2") (pintype "passive"))
      (node (ref "DA1") (pin "3") (pinfunction "TC_3") (pintype "passive"))
    )
    (net (code "51") (name "Net-(DA2-1C)") (class "Default")
      (node (ref "BA1") (pin "2") (pinfunction "2_2") (pintype "passive"))
      (node (ref "DA2") (pin "16") (pinfunction "1C_16") (pintype "open_collector"))
    )
    (net (code "52") (name "Net-(DD1B-NRST)") (class "Default")
      (node (ref "C11") (pin "2") (pinfunction "2_2") (pintype "passive"))
      (node (ref "DD1") (pin "7") (pinfunction "NRST_7") (pintype "input"))
      (node (ref "S1") (pin "1") (pintype "passive"))
      (node (ref "S1") (pin "2") (pintype "passive"))
    )
    (net (code "53") (name "Net-(DD1B-OSC32_IN)") (class "Default")
      (node (ref "C10") (pin "2") (pinfunction "2_2") (pintype "passive"))
      (node (ref "DD1") (pin "3") (pinfunction "OSC32_IN_3") (pintype "bidirectional"))
      (node (ref "Z1") (pin "1") (pinfunction "1_1") (pintype "passive"))
    )
    (net (code "54") (name "Net-(DD1B-OSC32_OUT)") (class "Default")
      (node (ref "C12") (pin "2") (pinfunction "2_2") (pintype "passive"))
      (node (ref "DD1") (pin "4") (pinfunction "OSC32_OUT_4") (pintype "bidirectional"))
      (node (ref "Z1") (pin "2") (pinfunction "2_2") (pintype "passive"))
    )
    (net (code "55") (name "Net-(DD1B-OSC_IN)") (class "Default")
      (node (ref "C13") (pin "2") (pinfunction "2_2") (pintype "passive"))
      (node (ref "DD1") (pin "5") (pinfunction "OSC_IN_5") (pintype "bidirectional"))
      (node (ref "Z2") (pin "1") (pinfunction "1_1") (pintype "passive"))
    )
    (net (code "56") (name "Net-(DD1B-OSC_OUT)") (class "Default")
      (node (ref "C15") (pin "2") (pinfunction "2_2") (pintype "passive"))
      (node (ref "DD1") (pin "6") (pinfunction "OSC_OUT_6") (pintype "bidirectional"))
      (node (ref "Z2") (pin "3") (pinfunction "3_3") (pintype "passive"))
    )
    (net (code "57") (name "Net-(DD1B-SWCLK)") (class "Default")
      (node (ref "DD1") (pin "49") (pinfunction "SWCLK_49") (pintype "bidirectional"))
      (node (ref "X6") (pin "1") (pinfunction "1_1") (pintype "passive"))
    )
    (net (code "58") (name "Net-(DD1B-SWDIO)") (class "Default")
      (node (ref "DD1") (pin "46") (pinfunction "SWDIO_46") (pintype "bidirectional"))
      (node (ref "X6") (pin "2") (pinfunction "2_2") (pintype "passive"))
    )
    (net (code "59") (name "Net-(R1-Pad2)") (class "Default")
      (node (ref "R1") (pin "2") (pinfunction "2_2") (pintype "passive"))
      (node (ref "X4") (pin "1") (pinfunction "1_1") (pintype "passive"))
    )
    (net (code "60") (name "Net-(R2-Pad2)") (class "Default")
      (node (ref "R2") (pin "2") (pinfunction "2_2") (pintype "passive"))
      (node (ref "X1") (pin "2") (pinfunction "2_2") (pintype "passive"))
    )
    (net (code "61") (name "Net-(R3-Pad2)") (class "Default")
      (node (ref "R3") (pin "2") (pinfunction "2_2") (pintype "passive"))
      (node (ref "X2") (pin "2") (pinfunction "2_2") (pintype "passive"))
    )
    (net (code "62") (name "Net-(R4-Pad2)") (class "Default")
      (node (ref "R4") (pin "2") (pinfunction "2_2") (pintype "passive"))
      (node (ref "X5") (pin "1") (pinfunction "1_1") (pintype "passive"))
    )
    (net (code "63") (name "Net-(R5-Pad2)") (class "Default")
      (node (ref "R5") (pin "2") (pinfunction "2_2") (pintype "passive"))
      (node (ref "X5") (pin "7") (pinfunction "7_7") (pintype "passive"))
    )
    (net (code "64") (name "Net-(R7-Pad2)") (class "Default")
      (node (ref "R7") (pin "2") (pinfunction "2_2") (pintype "passive"))
      (node (ref "X5") (pin "3") (pinfunction "3_3") (pintype "passive"))
    )
    (net (code "65") (name "Net-(R8-Pad2)") (class "Default")
      (node (ref "R8") (pin "2") (pinfunction "2_2") (pintype "passive"))
      (node (ref "X4") (pin "2") (pinfunction "2_2") (pintype "passive"))
    )
    (net (code "66") (name "Net-(R12-Pad2)") (class "Default")
      (node (ref "R12") (pin "2") (pinfunction "2_2") (pintype "passive"))
      (node (ref "X5") (pin "5") (pinfunction "5_5") (pintype "passive"))
    )
    (net (code "67") (name "Net-(R20-Pad1)") (class "Default")
      (node (ref "R20") (pin "1") (pinfunction "1_1") (pintype "passive"))
      (node (ref "R22") (pin "2") (pinfunction "2_2") (pintype "passive"))
      (node (ref "VT1") (pin "2") (pinfunction "2_2") (pintype "passive"))
    )
    (net (code "68") (name "Net-(R21-Pad1)") (class "Default")
      (node (ref "R21") (pin "1") (pinfunction "1_1") (pintype "passive"))
      (node (ref "R23") (pin "2") (pinfunction "2_2") (pintype "passive"))
      (node (ref "VT1") (pin "4") (pinfunction "4_4") (pintype "passive"))
    )
    (net (code "69") (name "Net-(R24-Pad1)") (class "Default")
      (node (ref "R24") (pin "1") (pinfunction "1_1") (pintype "passive"))
      (node (ref "X11") (pin "1") (pinfunction "1_1") (pintype "passive"))
    )
    (net (code "70") (name "Net-(R25-Pad1)") (class "Default")
      (node (ref "R25") (pin "1") (pinfunction "1_1") (pintype "passive"))
      (node (ref "X12") (pin "1") (pinfunction "1_1") (pintype "passive"))
    )
    (net (code "71") (name "Net-(R26-Pad1)") (class "Default")
      (node (ref "R26") (pin "1") (pinfunction "1_1") (pintype "passive"))
      (node (ref "X13") (pin "1") (pinfunction "1_1") (pintype "passive"))
    )
    (net (code "72") (name "Net-(R27-Pad1)") (class "Default")
      (node (ref "R27") (pin "1") (pinfunction "1_1") (pintype "passive"))
      (node (ref "X14") (pin "1") (pinfunction "1_1") (pintype "passive"))
    )
    (net (code "73") (name "Net-(R28-Pad1)") (class "Default")
      (node (ref "R28") (pin "1") (pinfunction "1_1") (pintype "passive"))
      (node (ref "X15") (pin "1") (pinfunction "1_1") (pintype "passive"))
    )
    (net (code "74") (name "Net-(R29-Pad1)") (class "Default")
      (node (ref "R29") (pin "1") (pinfunction "1_1") (pintype "passive"))
      (node (ref "X16") (pin "1") (pinfunction "1_1") (pintype "passive"))
    )
    (net (code "75") (name "Net-(R30-Pad1)") (class "Default")
      (node (ref "R30") (pin "1") (pinfunction "1_1") (pintype "passive"))
      (node (ref "VD2") (pin "2") (pinfunction "2_2") (pintype "passive"))
    )
    (net (code "76") (name "Net-(VT1-Pad5)") (class "Default")
      (node (ref "VT1") (pin "5") (pinfunction "5_5") (pintype "passive"))
      (node (ref "VT1") (pin "6") (pinfunction "6_6") (pintype "passive"))
      (node (ref "X18") (pin "1") (pinfunction "1_1") (pintype "passive"))
    )
    (net (code "77") (name "Net-(VT1-Pad7)") (class "Default")
      (node (ref "VT1") (pin "7") (pinfunction "7_7") (pintype "passive"))
      (node (ref "VT1") (pin "8") (pinfunction "8_8") (pintype "passive"))
      (node (ref "X17") (pin "1") (pinfunction "1_1") (pintype "passive"))
    )
    (net (code "78") (name "VCC_3V3") (class "Default")
      (node (ref "C1") (pin "2") (pinfunction "2_2") (pintype "passive"))
      (node (ref "C2") (pin "2") (pinfunction "2_2") (pintype "passive"))
      (node (ref "C20") (pin "1") (pinfunction "1_1") (pintype "passive"))
      (node (ref "C21") (pin "1") (pinfunction "1_1") (pintype "passive"))
      (node (ref "C3") (pin "2") (pinfunction "2_2") (pintype "passive"))
      (node (ref "C4") (pin "2") (pinfunction "2_2") (pintype "passive"))
      (node (ref "C5") (pin "1") (pinfunction "1_1") (pintype "passive"))
      (node (ref "C6") (pin "2") (pinfunction "2_2") (pintype "passive"))
      (node (ref "C7") (pin "1") (pinfunction "1_1") (pintype "passive"))
      (node (ref "DA4") (pin "2") (pinfunction "OUT_2") (pintype "power_in"))
      (node (ref "DD1") (pin "1") (pinfunction "VBAT_1") (pintype "power_in"))
      (node (ref "DD1") (pin "13") (pinfunction "VDDA_13") (pintype "power_in"))
      (node (ref "DD1") (pin "19") (pinfunction "VDD_19") (pintype "power_in"))
      (node (ref "DD1") (pin "32") (pinfunction "VDD_32") (pintype "power_in"))
      (node (ref "DD1") (pin "48") (pinfunction "VDD_48") (pintype "power_in"))
      (node (ref "DD1") (pin "64") (pinfunction "VDD_64") (pintype "power_in"))
      (node (ref "R30") (pin "2") (pinfunction "2_2") (pintype "passive"))
      (node (ref "X6") (pin "3") (pinfunction "3_3") (pintype "passive"))
    )
    (net (code "79") (name "VCC_5V0") (class "Default")
      (node (ref "C16") (pin "1") (pinfunction "1_1") (pintype "passive"))
      (node (ref "C17") (pin "1") (pinfunction "1_1") (pintype "passive"))
      (node (ref "C18") (pin "1") (pinfunction "1_1") (pintype "passive"))
      (node (ref "C19") (pin "1") (pinfunction "1_1") (pintype "passive"))
      (node (ref "DA4") (pin "3") (pinfunction "IN_3") (pintype "power_in"))
      (node (ref "L1") (pin "2") (pinfunction "2_2") (pintype "passive"))
      (node (ref "R19") (pin "1") (pinfunction "1_1") (pintype "passive"))
    )
    (net (code "80") (name "VCC_12V") (class "Default")
      (node (ref "BA1") (pin "1") (pinfunction "1_1") (pintype "passive"))
      (node (ref "C8") (pin "1") (pinfunction "1_1") (pintype "passive"))
      (node (ref "C9") (pin "1") (pinfunction "1_1") (pintype "passive"))
      (node (ref "DA1") (pin "6") (pinfunction "Vcc_6") (pintype "passive"))
      (node (ref "DA2") (pin "9") (pinfunction "COM_9") (pintype "power_in"))
      (node (ref "DA3") (pin "9") (pinfunction "COM_9") (pintype "power_in"))
      (node (ref "R15") (pin "2") (pinfunction "2_2") (pintype "passive"))
      (node (ref "R6") (pin "2") (pinfunction "2_2") (pintype "passive"))
      (node (ref "R9") (pin "2") (pinfunction "2_2") (pintype "passive"))
      (node (ref "X1") (pin "1") (pinfunction "1_1") (pintype "passive"))
      (node (ref "X10") (pin "2") (pinfunction "2_2") (pintype "passive"))
      (node (ref "X11") (pin "2") (pinfunction "2_2") (pintype "passive"))
      (node (ref "X12") (pin "2") (pinfunction "2_2") (pintype "passive"))
      (node (ref "X13") (pin "2") (pinfunction "2_2") (pintype "passive"))
      (node (ref "X14") (pin "2") (pinfunction "2_2") (pintype "passive"))
      (node (ref "X15") (pin "2") (pinfunction "2_2") (pintype "passive"))
      (node (ref "X16") (pin "2") (pinfunction "2_2") (pintype "passive"))
      (node (ref "X17") (pin "2") (pinfunction "2_2") (pintype "passive"))
      (node (ref "X18") (pin "2") (pinfunction "2_2") (pintype "passive"))
      (node (ref "X2") (pin "1") (pinfunction "1_1") (pintype "passive"))
      (node (ref "X3") (pin "2") (pinfunction "2_2") (pintype "passive"))
      (node (ref "X7") (pin "2") (pinfunction "2_2") (pintype "passive"))
      (node (ref "X9") (pin "2") (pinfunction "2_2") (pintype "passive"))
    )
    (net (code "81") (name "unconnected-(DA1-N.C.-Pad8)") (class "Default")
      (node (ref "DA1") (pin "8") (pinfunction "N.C._8") (pintype "passive"))
    )
    (net (code "82") (name "unconnected-(DA2-3B-Pad3)") (class "Default")
      (node (ref "DA2") (pin "3") (pinfunction "3B_3") (pintype "input"))
    )
    (net (code "83") (name "unconnected-(DA2-3C-Pad14)") (class "Default")
      (node (ref "DA2") (pin "14") (pinfunction "3C_14") (pintype "open_collector"))
    )
    (net (code "84") (name "unconnected-(DA2-4B-Pad4)") (class "Default")
      (node (ref "DA2") (pin "4") (pinfunction "4B_4") (pintype "input"))
    )
    (net (code "85") (name "unconnected-(DA2-4C-Pad13)") (class "Default")
      (node (ref "DA2") (pin "13") (pinfunction "4C_13") (pintype "open_collector"))
    )
    (net (code "86") (name "unconnected-(DD1A-PA15-Pad50)") (class "Default")
      (node (ref "DD1") (pin "50") (pinfunction "PA15_50") (pintype "bidirectional"))
    )
    (net (code "87") (name "unconnected-(DD1A-PB3-Pad55)") (class "Default")
      (node (ref "DD1") (pin "55") (pinfunction "PB3_55") (pintype "bidirectional"))
    )
    (net (code "88") (name "unconnected-(DD1A-PB4-Pad56)") (class "Default")
      (node (ref "DD1") (pin "56") (pinfunction "PB4_56") (pintype "bidirectional"))
    )
    (net (code "89") (name "unconnected-(DD1A-PB5-Pad57)") (class "Default")
      (node (ref "DD1") (pin "57") (pinfunction "PB5_57") (pintype "bidirectional"))
    )
    (net (code "90") (name "unconnected-(DD1A-PB8-Pad61)") (class "Default")
      (node (ref "DD1") (pin "61") (pinfunction "PB8_61") (pintype "bidirectional"))
    )
    (net (code "91") (name "unconnected-(DD1A-PB10-Pad29)") (class "Default")
      (node (ref "DD1") (pin "29") (pinfunction "PB10_29") (pintype "bidirectional"))
    )
    (net (code "92") (name "unconnected-(DD1A-PB13-Pad34)") (class "Default")
      (node (ref "DD1") (pin "34") (pinfunction "PB13_34") (pintype "bidirectional"))
    )
    (net (code "93") (name "unconnected-(DD1A-PB14-Pad35)") (class "Default")
      (node (ref "DD1") (pin "35") (pinfunction "PB14_35") (pintype "bidirectional"))
    )
    (net (code "94") (name "unconnected-(DD1A-PB15-Pad36)") (class "Default")
      (node (ref "DD1") (pin "36") (pinfunction "PB15_36") (pintype "bidirectional"))
    )
    (net (code "95") (name "unconnected-(DD1A-PC10-Pad51)") (class "Default")
      (node (ref "DD1") (pin "51") (pinfunction "PC10_51") (pintype "bidirectional"))
    )
    (net (code "96") (name "unconnected-(DD1A-PC13-Pad2)") (class "Default")
      (node (ref "DD1") (pin "2") (pinfunction "PC13_2") (pintype "bidirectional"))
    )
  )
)
